# as3320-Vowel-1.net
KiCad netlist of a schematic drawn in EAGLE
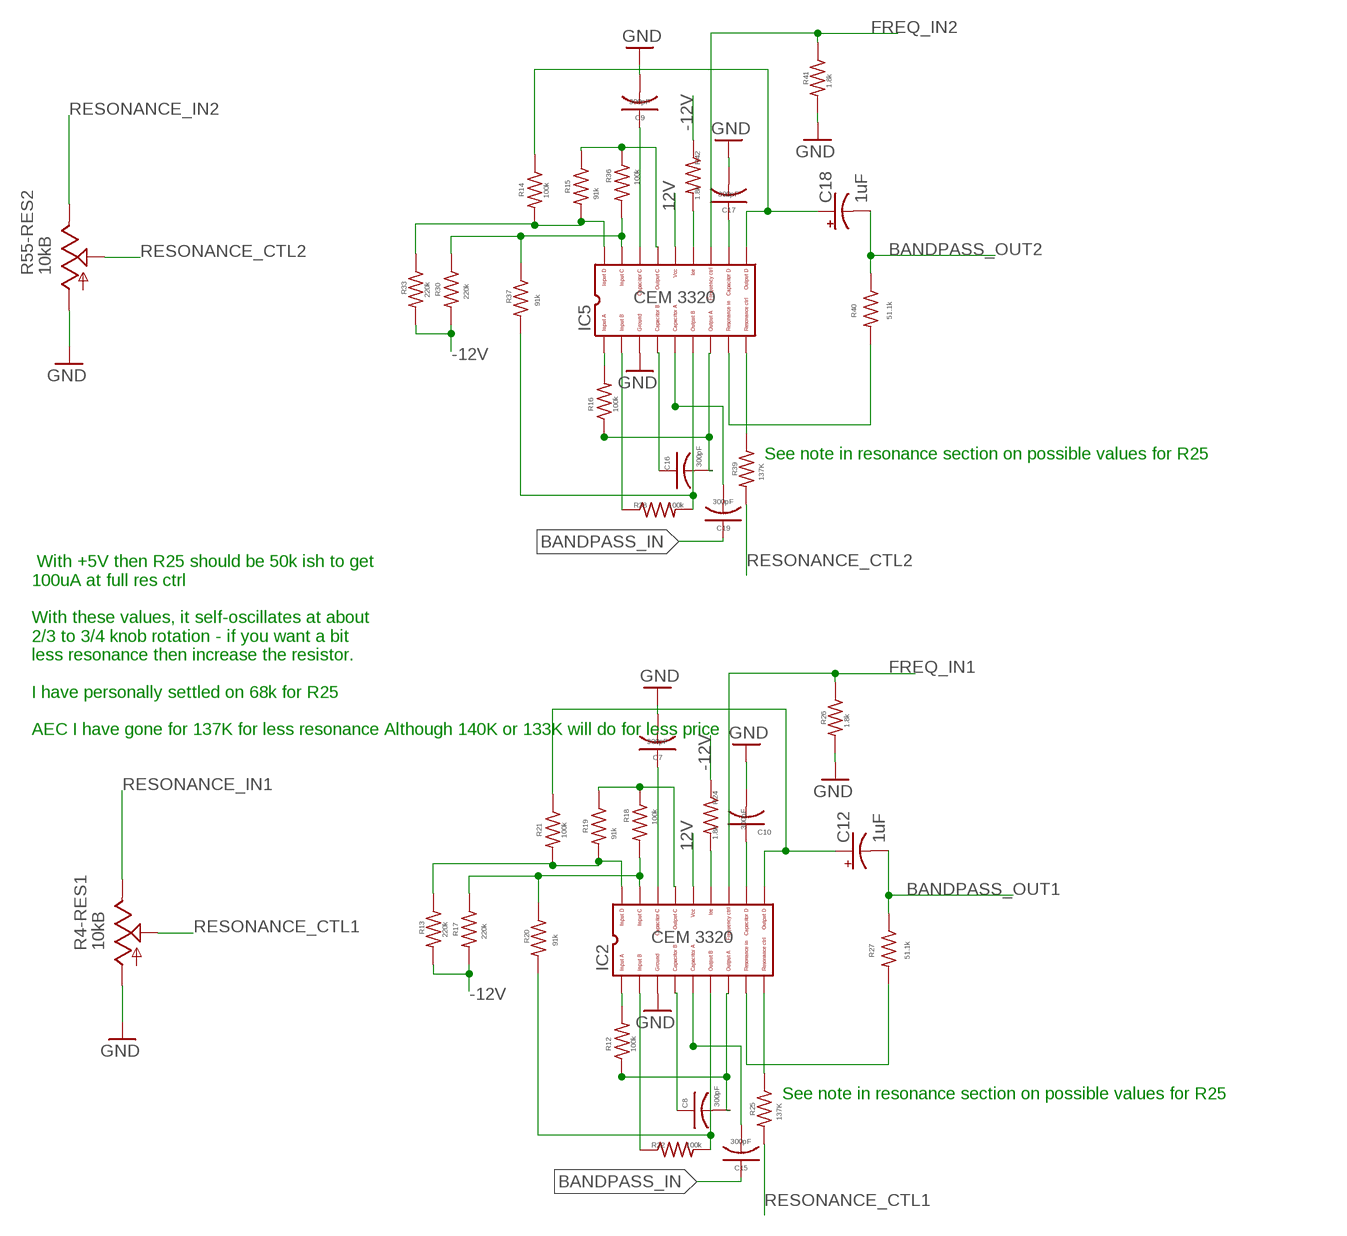
[diagram p0: schematic, sheet 1, part 1 of 2]
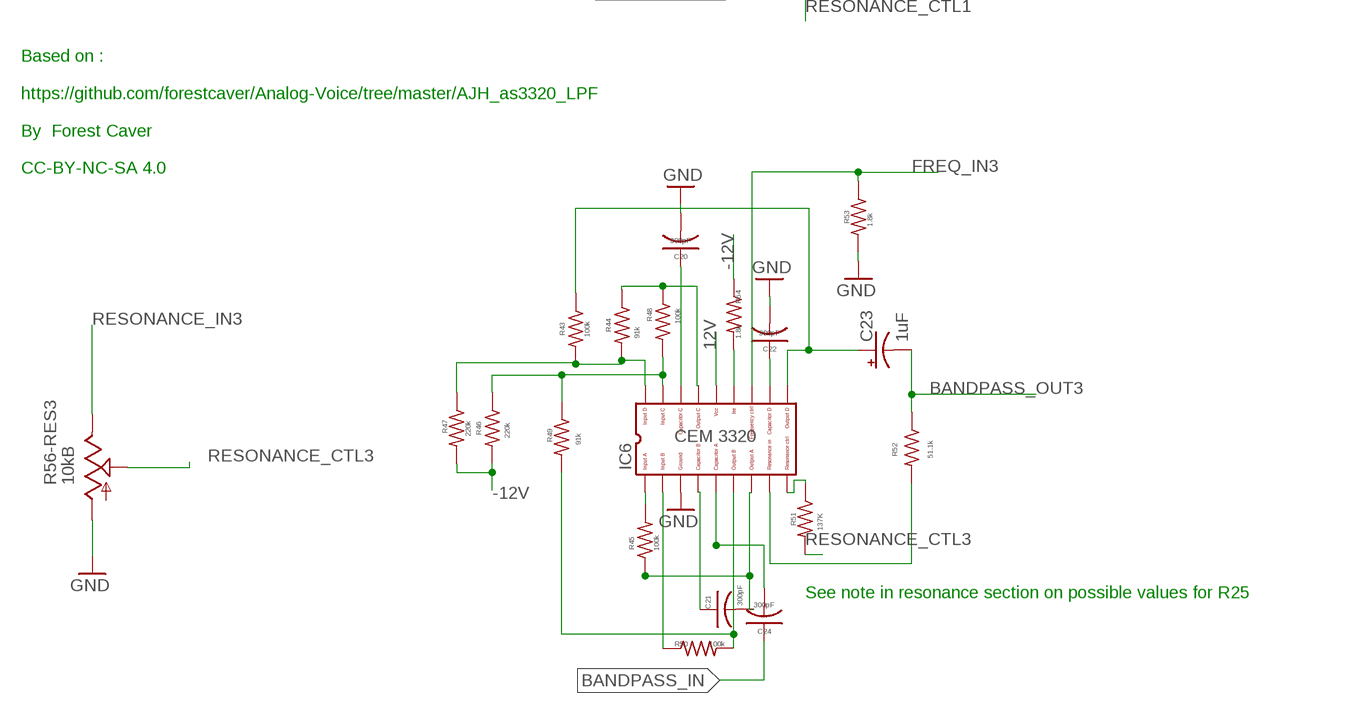
[diagram p1: schematic, sheet 1, part 2 of 2]
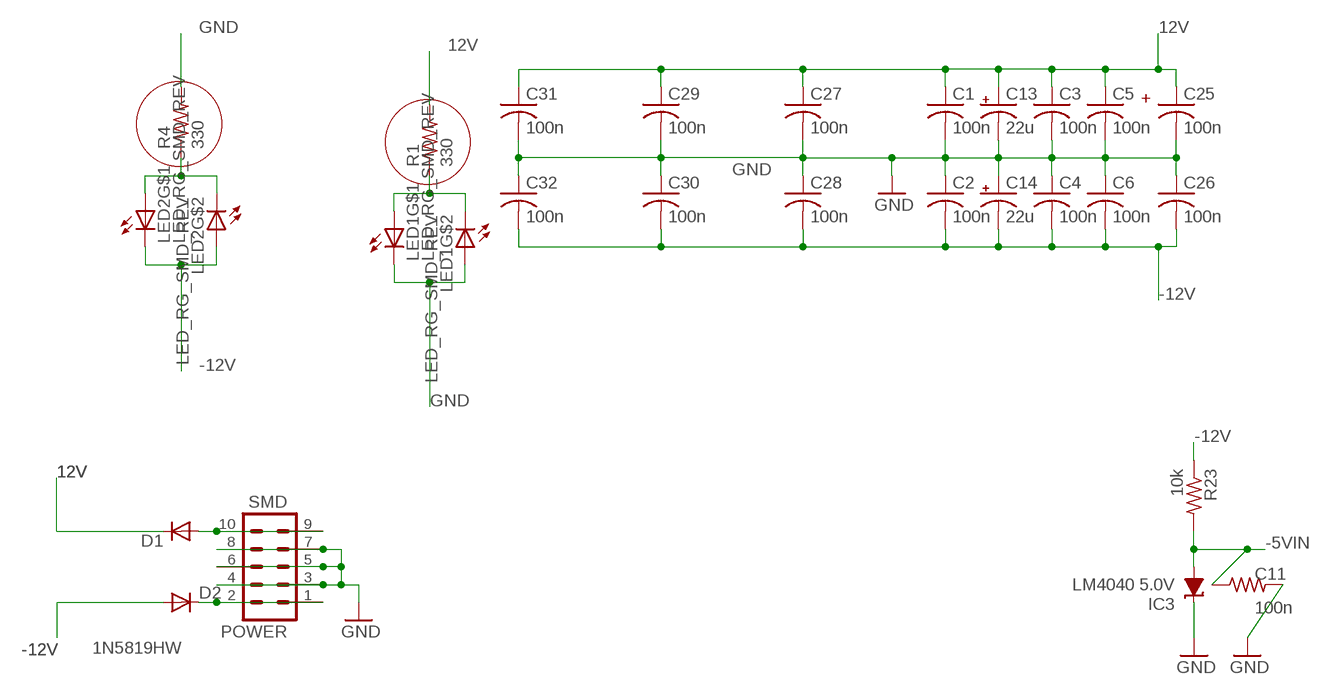
[diagram p2: schematic, sheet 2]
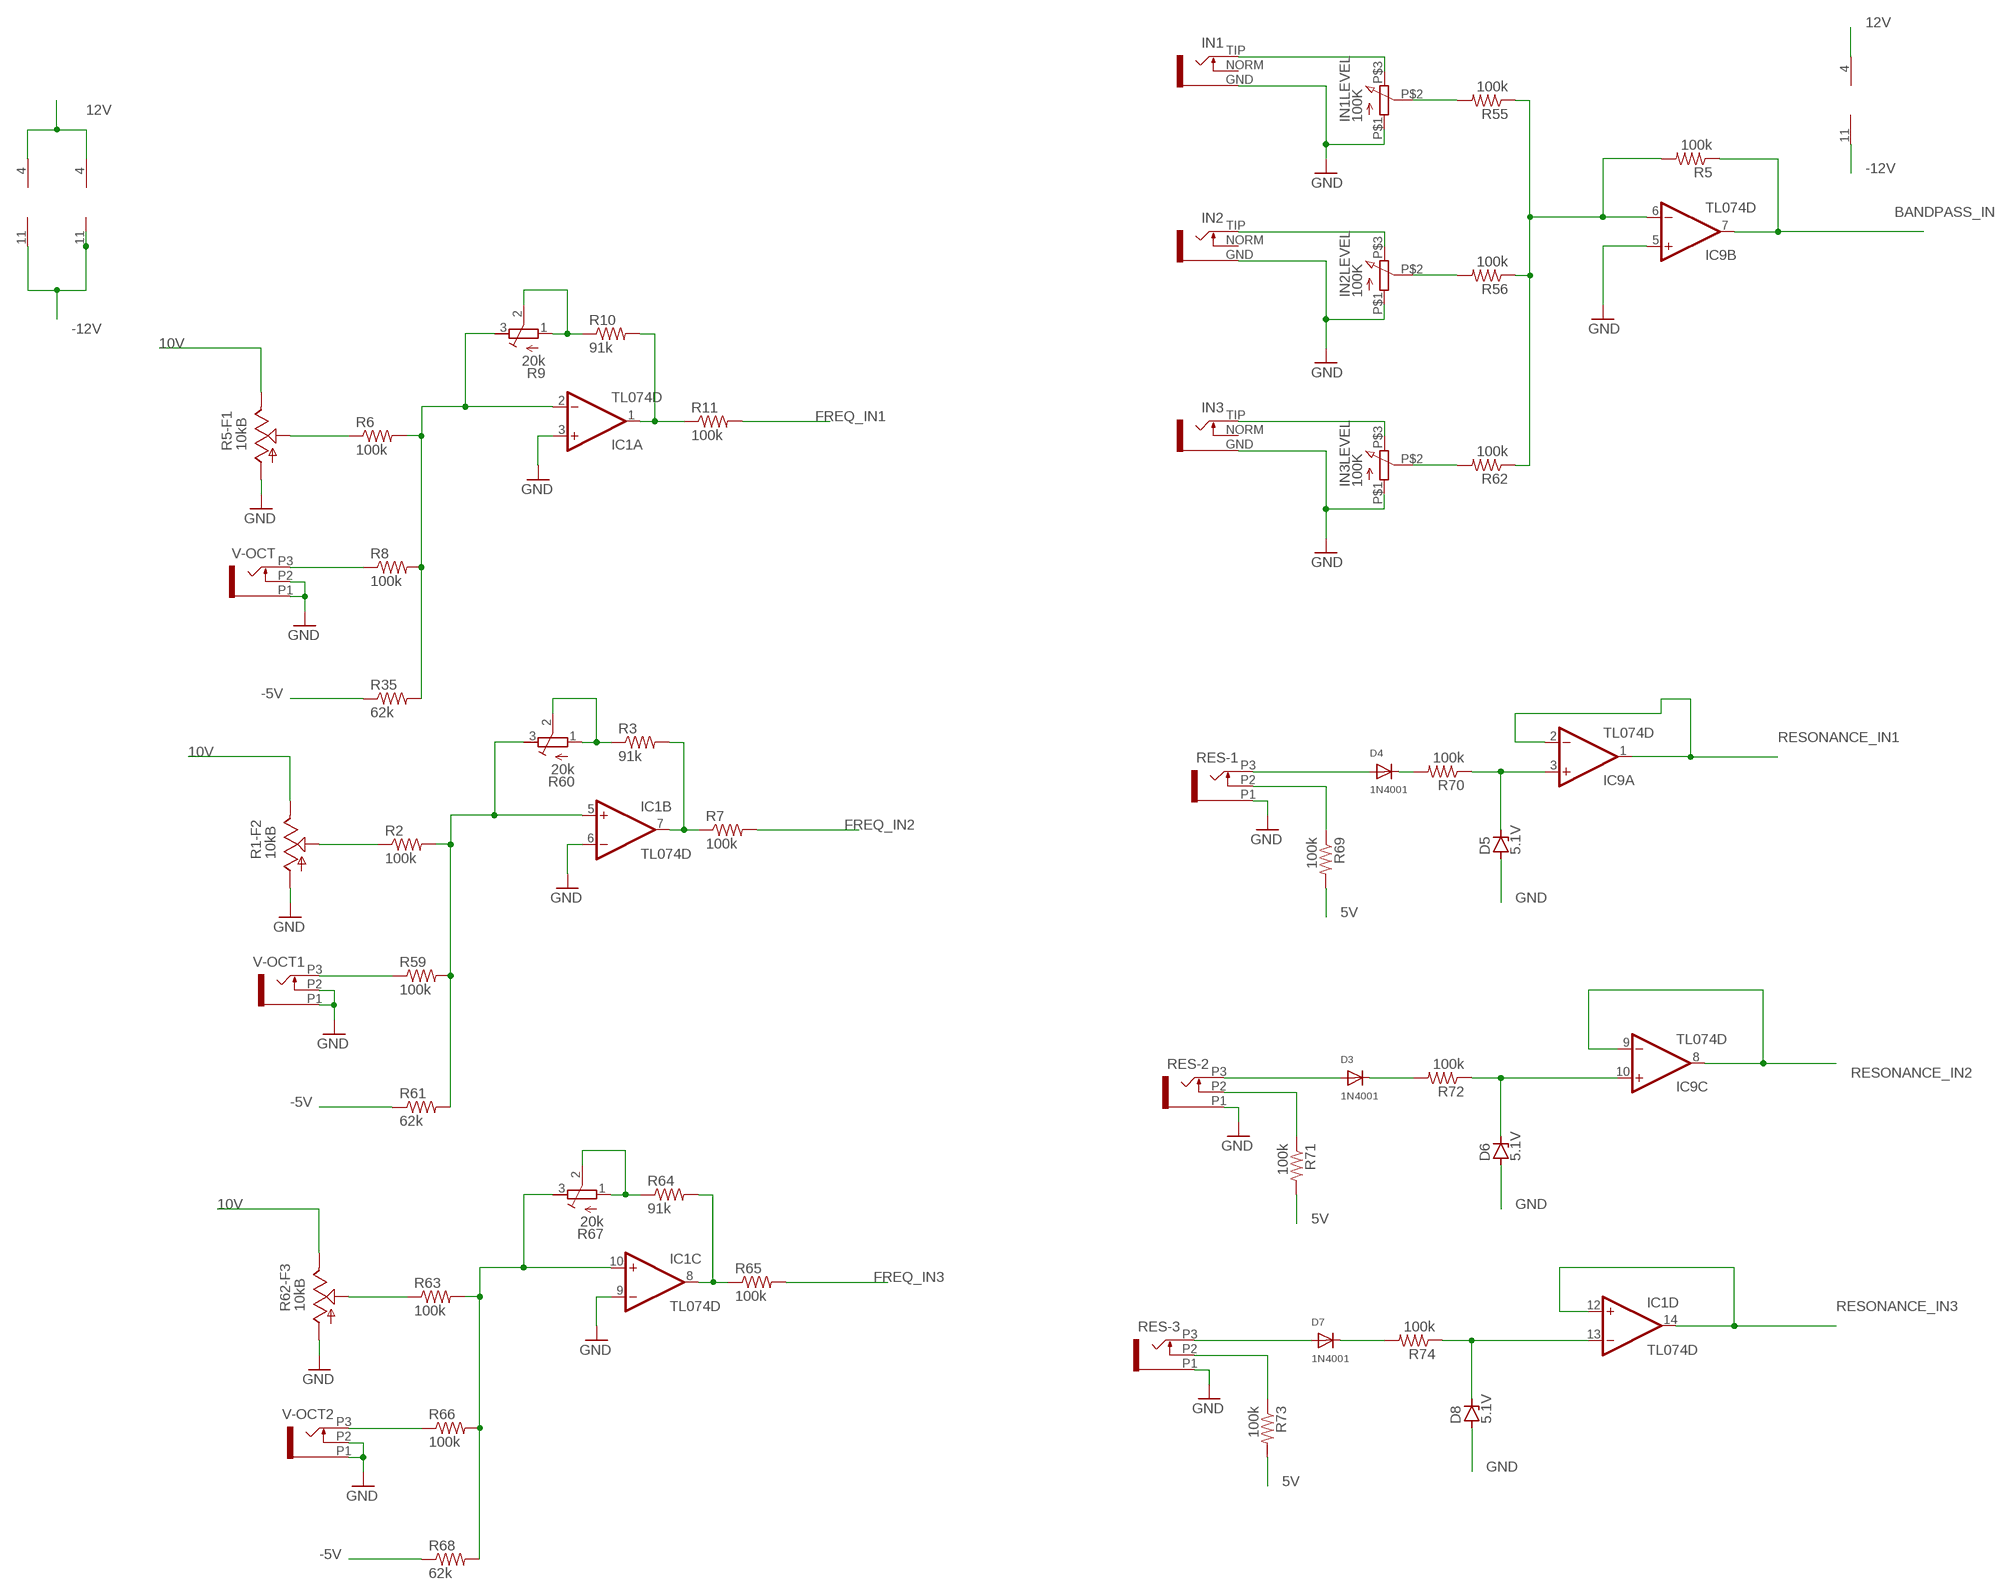
[diagram p3: schematic, sheet 3]
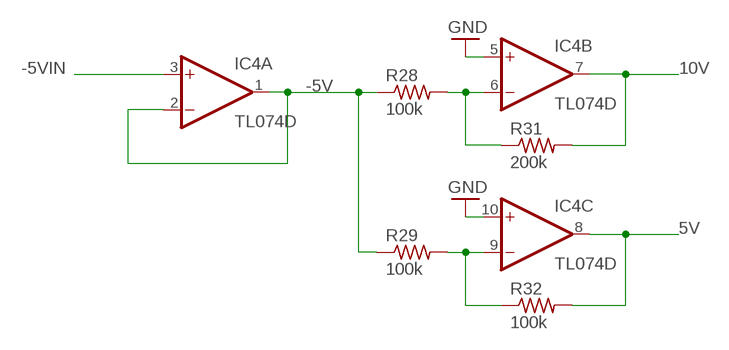
[diagram p4: schematic, sheet 4]
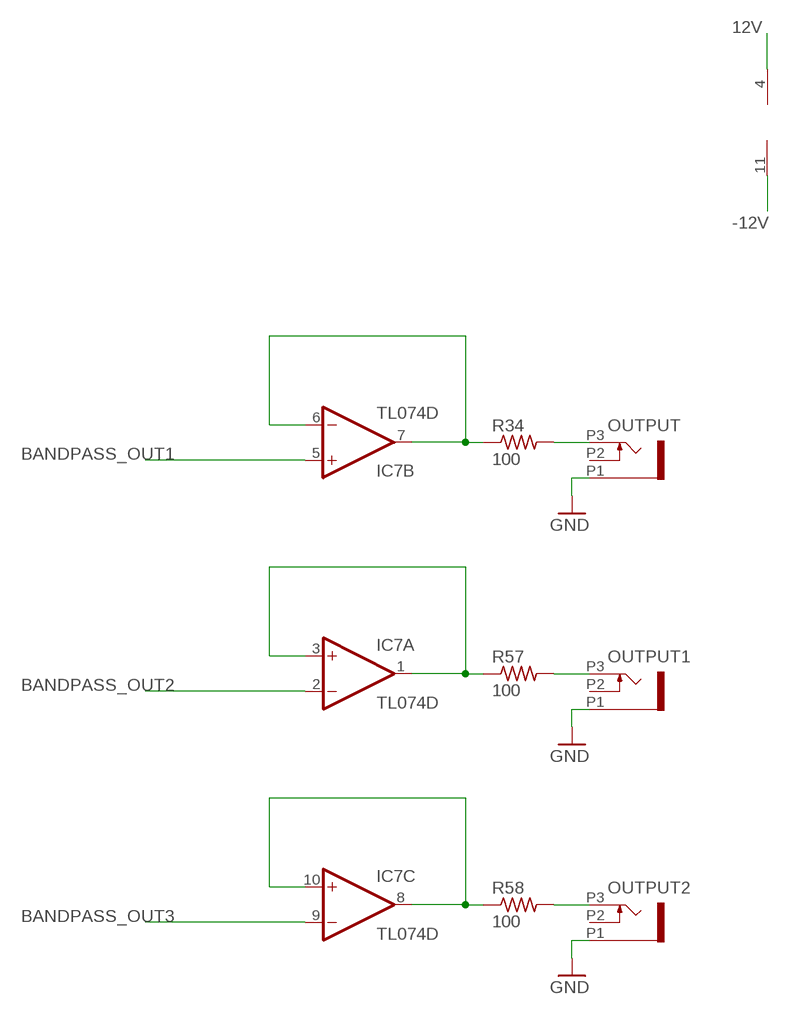
[diagram p5: schematic, sheet 5]

(export (version "E")
  (design (tool "Eeschema 10.0.6"))
  (components
    (comp (ref "IC4")
      (value "TL074D")
      (footprint "eagle-import:SO14")
      (libsource (lib "eagle-import") (part "linear_262_TL074D"))
    )
    (comp (ref "R28")
      (value "100k")
      (footprint "eagle-import:GMSN_M0805")
      (libsource (lib "eagle-import") (part "GMSN_R-US_M0805"))
    )
    (comp (ref "R29")
      (value "100k")
      (footprint "eagle-import:GMSN_M0805")
      (libsource (lib "eagle-import") (part "GMSN_R-US_M0805"))
    )
    (comp (ref "R31")
      (value "200k")
      (footprint "eagle-import:GMSN_M0805")
      (libsource (lib "eagle-import") (part "GMSN_R-US_M0805"))
    )
    (comp (ref "R32")
      (value "100k")
      (footprint "eagle-import:GMSN_M0805")
      (libsource (lib "eagle-import") (part "GMSN_R-US_M0805"))
    )
    (comp (ref "C1")
      (value "100n")
      (footprint "eagle-import:C0805K")
      (libsource (lib "eagle-import") (part "C-USC0805K"))
    )
    (comp (ref "C2")
      (value "100n")
      (footprint "eagle-import:C0805K")
      (libsource (lib "eagle-import") (part "C-USC0805K"))
    )
    (comp (ref "C3")
      (value "100n")
      (footprint "eagle-import:C0805K")
      (libsource (lib "eagle-import") (part "C-USC0805K"))
    )
    (comp (ref "C4")
      (value "100n")
      (footprint "eagle-import:C0805K")
      (libsource (lib "eagle-import") (part "C-USC0805K"))
    )
    (comp (ref "C5")
      (value "100n")
      (footprint "eagle-import:C0805K")
      (libsource (lib "eagle-import") (part "C-USC0805K"))
    )
    (comp (ref "C6")
      (value "100n")
      (footprint "eagle-import:C0805K")
      (libsource (lib "eagle-import") (part "C-USC0805K"))
    )
    (comp (ref "C11")
      (value "100n")
      (footprint "eagle-import:GMSN_M0805")
      (libsource (lib "eagle-import") (part "GMSN_R-US_M0805"))
    )
    (comp (ref "C13")
      (value "22u")
      (footprint "eagle-import:PANASONIC_B")
      (libsource (lib "eagle-import") (part "CPOL-USB"))
    )
    (comp (ref "C14")
      (value "22u")
      (footprint "eagle-import:PANASONIC_B")
      (libsource (lib "eagle-import") (part "CPOL-USB"))
    )
    (comp (ref "C25")
      (value "100n")
      (footprint "eagle-import:C0805K")
      (libsource (lib "eagle-import") (part "C-USC0805K"))
    )
    (comp (ref "C26")
      (value "100n")
      (footprint "eagle-import:C0805K")
      (libsource (lib "eagle-import") (part "C-USC0805K"))
    )
    (comp (ref "C27")
      (value "100n")
      (footprint "eagle-import:C0805K")
      (libsource (lib "eagle-import") (part "C-USC0805K"))
    )
    (comp (ref "C28")
      (value "100n")
      (footprint "eagle-import:C0805K")
      (libsource (lib "eagle-import") (part "C-USC0805K"))
    )
    (comp (ref "C29")
      (value "100n")
      (footprint "eagle-import:C0805K")
      (libsource (lib "eagle-import") (part "C-USC0805K"))
    )
    (comp (ref "C30")
      (value "100n")
      (footprint "eagle-import:C0805K")
      (libsource (lib "eagle-import") (part "C-USC0805K"))
    )
    (comp (ref "C31")
      (value "100n")
      (footprint "eagle-import:C0805K")
      (libsource (lib "eagle-import") (part "C-USC0805K"))
    )
    (comp (ref "C32")
      (value "100n")
      (footprint "eagle-import:C0805K")
      (libsource (lib "eagle-import") (part "C-USC0805K"))
    )
    (comp (ref "D1")
      (value "1N5819HW")
      (footprint "eagle-import:SOD123")
      (libsource (lib "eagle-import") (part "DIODE-SOD123"))
    )
    (comp (ref "D2")
      (value "1N5819HW")
      (footprint "eagle-import:SOD123")
      (libsource (lib "eagle-import") (part "DIODE-SOD123"))
    )
    (comp (ref "IC3")
      (value "LM4040 5.0V")
      (footprint "eagle-import:DBZ_R-PDSO-G3")
      (libsource (lib "eagle-import") (part "LM4041DBZC12"))
    )
    (comp (ref "LED1")
      (value "LED_RG_SMD_REV")
      (footprint "eagle-import:LSG_T77K")
      (fields (field (name "RS-PART") "915-4828"))
      (libsource (lib "eagle-import") (part "LED_RG_SMD_REV"))
    )
    (comp (ref "LED2")
      (value "LED_RG_SMD_REV")
      (footprint "eagle-import:LSG_T77K")
      (libsource (lib "eagle-import") (part "LED_RG_SMD_REV"))
    )
    (comp (ref "POWER")
      (value "SMD")
      (footprint "eagle-import:2X5-SHROUDED_SMD")
      (fields (field (name "RS-PART") "828-1783"))
      (libsource (lib "eagle-import") (part "CONN_05X2SHD_SMD"))
    )
    (comp (ref "R1")
      (value "330")
      (footprint "eagle-import:GMSN_M0805")
      (libsource (lib "eagle-import") (part "GMSN_R-US_M0805"))
    )
    (comp (ref "R4")
      (value "330")
      (footprint "eagle-import:GMSN_M0805")
      (fields (field (name "RS-PART") "915-4828"))
      (libsource (lib "eagle-import") (part "GMSN_R-US_M0805"))
    )
    (comp (ref "R23")
      (value "10k")
      (footprint "eagle-import:GMSN_M0805")
      (libsource (lib "eagle-import") (part "GMSN_R-US_M0805"))
    )
    (comp (ref "C7")
      (value "300pF")
      (footprint "eagle-import:C0805K")
      (libsource (lib "eagle-import") (part "C-USC0805K"))
    )
    (comp (ref "C8")
      (value "300pF")
      (footprint "eagle-import:C0805K")
      (libsource (lib "eagle-import") (part "C-USC0805K"))
    )
    (comp (ref "C9")
      (value "300pF")
      (footprint "eagle-import:C0805K")
      (libsource (lib "eagle-import") (part "C-USC0805K"))
    )
    (comp (ref "C10")
      (value "300pF")
      (footprint "eagle-import:GMSN_C0805K")
      (libsource (lib "eagle-import") (part "GMSN_C-USC0805K"))
    )
    (comp (ref "C12")
      (value "1uF")
      (footprint "eagle-import:PANASONIC_B")
      (libsource (lib "eagle-import") (part "rcl_334_CPOL-USB"))
    )
    (comp (ref "C15")
      (value "300pF")
      (footprint "eagle-import:C0805K")
      (libsource (lib "eagle-import") (part "C-USC0805K"))
    )
    (comp (ref "C16")
      (value "300pF")
      (footprint "eagle-import:C0805K")
      (libsource (lib "eagle-import") (part "C-USC0805K"))
    )
    (comp (ref "C17")
      (value "300pF")
      (footprint "eagle-import:C0805K")
      (libsource (lib "eagle-import") (part "C-USC0805K"))
    )
    (comp (ref "C18")
      (value "1uF")
      (footprint "eagle-import:PANASONIC_B")
      (libsource (lib "eagle-import") (part "rcl_334_CPOL-USB"))
    )
    (comp (ref "C19")
      (value "300pF")
      (footprint "eagle-import:C0805K")
      (libsource (lib "eagle-import") (part "C-USC0805K"))
    )
    (comp (ref "C20")
      (value "300pF")
      (footprint "eagle-import:C0805K")
      (libsource (lib "eagle-import") (part "C-USC0805K"))
    )
    (comp (ref "C21")
      (value "300pF")
      (footprint "eagle-import:C0805K")
      (libsource (lib "eagle-import") (part "C-USC0805K"))
    )
    (comp (ref "C22")
      (value "300pF")
      (footprint "eagle-import:C0805K")
      (libsource (lib "eagle-import") (part "C-USC0805K"))
    )
    (comp (ref "C23")
      (value "1uF")
      (footprint "eagle-import:PANASONIC_B")
      (libsource (lib "eagle-import") (part "rcl_334_CPOL-USB"))
    )
    (comp (ref "C24")
      (value "300pF")
      (footprint "eagle-import:GMSN_C0805K")
      (libsource (lib "eagle-import") (part "GMSN_C-USC0805K"))
    )
    (comp (ref "IC2")
      (value "CEM3320")
      (footprint "eagle-import:DIL18")
      (libsource (lib "eagle-import") (part "CEM3320"))
    )
    (comp (ref "IC5")
      (value "CEM3320")
      (footprint "eagle-import:DIL18")
      (libsource (lib "eagle-import") (part "CEM3320"))
    )
    (comp (ref "IC6")
      (value "CEM3320")
      (footprint "eagle-import:DIL18")
      (libsource (lib "eagle-import") (part "CEM3320"))
    )
    (comp (ref "R4-RES1")
      (value "10kB")
      (footprint "eagle-import:ALPS_POT_VERTICAL")
      (libsource (lib "eagle-import") (part "POT_USVERTICAL"))
    )
    (comp (ref "R12")
      (value "100k")
      (footprint "eagle-import:GMSN_M0805")
      (libsource (lib "eagle-import") (part "GMSN_R-US_M0805"))
    )
    (comp (ref "R13")
      (value "220k")
      (footprint "eagle-import:GMSN_M0805")
      (libsource (lib "eagle-import") (part "GMSN_R-US_M0805"))
    )
    (comp (ref "R14")
      (value "100k")
      (footprint "eagle-import:GMSN_M0805")
      (libsource (lib "eagle-import") (part "GMSN_R-US_M0805"))
    )
    (comp (ref "R15")
      (value "91k")
      (footprint "eagle-import:GMSN_M0805")
      (libsource (lib "eagle-import") (part "GMSN_R-US_M0805"))
    )
    (comp (ref "R16")
      (value "100k")
      (footprint "eagle-import:GMSN_M0805")
      (libsource (lib "eagle-import") (part "GMSN_R-US_M0805"))
    )
    (comp (ref "R17")
      (value "220k")
      (footprint "eagle-import:GMSN_M0805")
      (libsource (lib "eagle-import") (part "GMSN_R-US_M0805"))
    )
    (comp (ref "R18")
      (value "100k")
      (footprint "eagle-import:GMSN_M0805")
      (libsource (lib "eagle-import") (part "GMSN_R-US_M0805"))
    )
    (comp (ref "R19")
      (value "91k")
      (footprint "eagle-import:GMSN_M0805")
      (libsource (lib "eagle-import") (part "GMSN_R-US_M0805"))
    )
    (comp (ref "R20")
      (value "91k")
      (footprint "eagle-import:GMSN_M0805")
      (libsource (lib "eagle-import") (part "GMSN_R-US_M0805"))
    )
    (comp (ref "R21")
      (value "100k")
      (footprint "eagle-import:GMSN_M0805")
      (libsource (lib "eagle-import") (part "GMSN_R-US_M0805"))
    )
    (comp (ref "R22")
      (value "100k")
      (footprint "eagle-import:GMSN_M0805")
      (libsource (lib "eagle-import") (part "GMSN_R-US_M0805"))
    )
    (comp (ref "R24")
      (value "1.8k")
      (footprint "eagle-import:GMSN_M0805")
      (libsource (lib "eagle-import") (part "GMSN_R-US_M0805"))
    )
    (comp (ref "R25")
      (value "137K")
      (footprint "eagle-import:GMSN_M0805")
      (libsource (lib "eagle-import") (part "GMSN_R-US_M0805"))
    )
    (comp (ref "R26")
      (value "1.8k")
      (footprint "eagle-import:GMSN_M0805")
      (libsource (lib "eagle-import") (part "GMSN_R-US_M0805"))
    )
    (comp (ref "R27")
      (value "51.1k")
      (footprint "eagle-import:GMSN_M0805")
      (libsource (lib "eagle-import") (part "GMSN_R-US_M0805"))
    )
    (comp (ref "R30")
      (value "220k")
      (footprint "eagle-import:GMSN_M0805")
      (libsource (lib "eagle-import") (part "GMSN_R-US_M0805"))
    )
    (comp (ref "R33")
      (value "220k")
      (footprint "eagle-import:GMSN_M0805")
      (libsource (lib "eagle-import") (part "GMSN_R-US_M0805"))
    )
    (comp (ref "R36")
      (value "100k")
      (footprint "eagle-import:GMSN_M0805")
      (libsource (lib "eagle-import") (part "GMSN_R-US_M0805"))
    )
    (comp (ref "R37")
      (value "91k")
      (footprint "eagle-import:GMSN_M0805")
      (libsource (lib "eagle-import") (part "GMSN_R-US_M0805"))
    )
    (comp (ref "R38")
      (value "100k")
      (footprint "eagle-import:GMSN_M0805")
      (libsource (lib "eagle-import") (part "GMSN_R-US_M0805"))
    )
    (comp (ref "R39")
      (value "137K")
      (footprint "eagle-import:GMSN_M0805")
      (libsource (lib "eagle-import") (part "GMSN_R-US_M0805"))
    )
    (comp (ref "R40")
      (value "51.1k")
      (footprint "eagle-import:GMSN_M0805")
      (libsource (lib "eagle-import") (part "GMSN_R-US_M0805"))
    )
    (comp (ref "R41")
      (value "1.8k")
      (footprint "eagle-import:GMSN_M0805")
      (libsource (lib "eagle-import") (part "GMSN_R-US_M0805"))
    )
    (comp (ref "R42")
      (value "1.8k")
      (footprint "eagle-import:GMSN_M0805")
      (libsource (lib "eagle-import") (part "GMSN_R-US_M0805"))
    )
    (comp (ref "R43")
      (value "100k")
      (footprint "eagle-import:GMSN_M0805")
      (libsource (lib "eagle-import") (part "GMSN_R-US_M0805"))
    )
    (comp (ref "R44")
      (value "91k")
      (footprint "eagle-import:GMSN_M0805")
      (libsource (lib "eagle-import") (part "GMSN_R-US_M0805"))
    )
    (comp (ref "R45")
      (value "100k")
      (footprint "eagle-import:GMSN_M0805")
      (libsource (lib "eagle-import") (part "GMSN_R-US_M0805"))
    )
    (comp (ref "R46")
      (value "220k")
      (footprint "eagle-import:GMSN_M0805")
      (libsource (lib "eagle-import") (part "GMSN_R-US_M0805"))
    )
    (comp (ref "R47")
      (value "220k")
      (footprint "eagle-import:GMSN_M0805")
      (libsource (lib "eagle-import") (part "GMSN_R-US_M0805"))
    )
    (comp (ref "R48")
      (value "100k")
      (footprint "eagle-import:GMSN_M0805")
      (libsource (lib "eagle-import") (part "GMSN_R-US_M0805"))
    )
    (comp (ref "R49")
      (value "91k")
      (footprint "eagle-import:GMSN_M0805")
      (libsource (lib "eagle-import") (part "GMSN_R-US_M0805"))
    )
    (comp (ref "R50")
      (value "100k")
      (footprint "eagle-import:GMSN_M0805")
      (libsource (lib "eagle-import") (part "GMSN_R-US_M0805"))
    )
    (comp (ref "R51")
      (value "137K")
      (footprint "eagle-import:GMSN_M0805")
      (libsource (lib "eagle-import") (part "GMSN_R-US_M0805"))
    )
    (comp (ref "R52")
      (value "51.1k")
      (footprint "eagle-import:GMSN_M0805")
      (libsource (lib "eagle-import") (part "GMSN_R-US_M0805"))
    )
    (comp (ref "R53")
      (value "1.8k")
      (footprint "eagle-import:GMSN_M0805")
      (libsource (lib "eagle-import") (part "GMSN_R-US_M0805"))
    )
    (comp (ref "R54")
      (value "1.8k")
      (footprint "eagle-import:GMSN_M0805")
      (libsource (lib "eagle-import") (part "GMSN_R-US_M0805"))
    )
    (comp (ref "R55-RES2")
      (value "10kB")
      (footprint "eagle-import:ALPS_POT_VERTICAL")
      (libsource (lib "eagle-import") (part "POT_USVERTICAL"))
    )
    (comp (ref "R56-RES3")
      (value "10kB")
      (footprint "eagle-import:ALPS_POT_VERTICAL")
      (libsource (lib "eagle-import") (part "POT_USVERTICAL"))
    )
    (comp (ref "D3")
      (value "1N4001")
      (footprint "eagle-import:SMADIODE")
      (libsource (lib "eagle-import") (part "DIODESMA"))
    )
    (comp (ref "D4")
      (value "1N4001")
      (footprint "eagle-import:SMADIODE")
      (libsource (lib "eagle-import") (part "DIODESMA"))
    )
    (comp (ref "D5")
      (value "5.1V")
      (footprint "eagle-import:SOT23")
      (fields (field (name "RS-PART") "816-7962"))
      (libsource (lib "eagle-import") (part "ZENER-DIODESOT23"))
    )
    (comp (ref "D6")
      (value "5.1V")
      (footprint "eagle-import:SOT23")
      (fields (field (name "RS-PART") "816-7962"))
      (libsource (lib "eagle-import") (part "ZENER-DIODESOT23"))
    )
    (comp (ref "D7")
      (value "1N4001")
      (footprint "eagle-import:SMADIODE")
      (libsource (lib "eagle-import") (part "DIODESMA"))
    )
    (comp (ref "D8")
      (value "5.1V")
      (footprint "eagle-import:SOT23")
      (fields (field (name "RS-PART") "816-7962"))
      (libsource (lib "eagle-import") (part "ZENER-DIODESOT23"))
    )
    (comp (ref "IC1")
      (value "TL074D")
      (footprint "eagle-import:SO14")
      (libsource (lib "eagle-import") (part "linear_262_TL074D"))
    )
    (comp (ref "IC9")
      (value "TL074D")
      (footprint "eagle-import:SO14")
      (libsource (lib "eagle-import") (part "TL074D"))
    )
    (comp (ref "IN1")
      (value "S_JACK")
      (footprint "eagle-import:S_JACK")
      (libsource (lib "eagle-import") (part "S_JACK"))
    )
    (comp (ref "IN1LEVEL")
      (value "100K")
      (footprint "eagle-import:POT")
      (libsource (lib "eagle-import") (part "9MMPOT"))
    )
    (comp (ref "IN2")
      (value "S_JACK")
      (footprint "eagle-import:S_JACK")
      (libsource (lib "eagle-import") (part "S_JACK"))
    )
    (comp (ref "IN2LEVEL")
      (value "100K")
      (footprint "eagle-import:POT")
      (libsource (lib "eagle-import") (part "9MMPOT"))
    )
    (comp (ref "IN3")
      (value "S_JACK")
      (footprint "eagle-import:S_JACK")
      (libsource (lib "eagle-import") (part "S_JACK"))
    )
    (comp (ref "IN3LEVEL")
      (value "100K")
      (footprint "eagle-import:POT")
      (libsource (lib "eagle-import") (part "9MMPOT"))
    )
    (comp (ref "R1-F2")
      (value "10kB")
      (footprint "eagle-import:ALPS_POT_VERTICAL")
      (libsource (lib "eagle-import") (part "POT_USVERTICAL"))
    )
    (comp (ref "R2")
      (value "100k")
      (footprint "eagle-import:GMSN_M0805")
      (libsource (lib "eagle-import") (part "GMSN_R-US_M0805"))
    )
    (comp (ref "R3")
      (value "91k")
      (footprint "eagle-import:GMSN_M0805")
      (libsource (lib "eagle-import") (part "GMSN_R-US_M0805"))
    )
    (comp (ref "R5")
      (value "100k")
      (footprint "eagle-import:GMSN_M0805")
      (libsource (lib "eagle-import") (part "GMSN_R-US_M0805"))
    )
    (comp (ref "R5-F1")
      (value "10kB")
      (footprint "eagle-import:ALPS_POT_VERTICAL")
      (libsource (lib "eagle-import") (part "POT_USVERTICAL"))
    )
    (comp (ref "R6")
      (value "100k")
      (footprint "eagle-import:GMSN_M0805")
      (libsource (lib "eagle-import") (part "GMSN_R-US_M0805"))
    )
    (comp (ref "R7")
      (value "100k")
      (footprint "eagle-import:GMSN_M0805")
      (libsource (lib "eagle-import") (part "GMSN_R-US_M0805"))
    )
    (comp (ref "R8")
      (value "100k")
      (footprint "eagle-import:GMSN_M0805")
      (libsource (lib "eagle-import") (part "GMSN_R-US_M0805"))
    )
    (comp (ref "R9")
      (value "20k")
      (footprint "eagle-import:RTRIM3296X")
      (libsource (lib "eagle-import") (part "R-TRIMM3296X"))
    )
    (comp (ref "R10")
      (value "91k")
      (footprint "eagle-import:GMSN_M0805")
      (libsource (lib "eagle-import") (part "GMSN_R-US_M0805"))
    )
    (comp (ref "R11")
      (value "100k")
      (footprint "eagle-import:GMSN_M0805")
      (libsource (lib "eagle-import") (part "GMSN_R-US_M0805"))
    )
    (comp (ref "R35")
      (value "62k")
      (footprint "eagle-import:GMSN_M0805")
      (libsource (lib "eagle-import") (part "GMSN_R-US_M0805"))
    )
    (comp (ref "R55")
      (value "100k")
      (footprint "eagle-import:R0805")
      (libsource (lib "eagle-import") (part "GMSN_R-US_R0805"))
    )
    (comp (ref "R56")
      (value "100k")
      (footprint "eagle-import:R0805")
      (libsource (lib "eagle-import") (part "GMSN_R-US_R0805"))
    )
    (comp (ref "R59")
      (value "100k")
      (footprint "eagle-import:GMSN_M0805")
      (libsource (lib "eagle-import") (part "GMSN_R-US_M0805"))
    )
    (comp (ref "R60")
      (value "20k")
      (footprint "eagle-import:RTRIM3296X")
      (libsource (lib "eagle-import") (part "R-TRIMM3296X"))
    )
    (comp (ref "R61")
      (value "62k")
      (footprint "eagle-import:GMSN_M0805")
      (libsource (lib "eagle-import") (part "GMSN_R-US_M0805"))
    )
    (comp (ref "R62")
      (value "100k")
      (footprint "eagle-import:R0805")
      (libsource (lib "eagle-import") (part "GMSN_R-US_R0805"))
    )
    (comp (ref "R62-F3")
      (value "10kB")
      (footprint "eagle-import:ALPS_POT_VERTICAL")
      (libsource (lib "eagle-import") (part "POT_USVERTICAL"))
    )
    (comp (ref "R63")
      (value "100k")
      (footprint "eagle-import:GMSN_M0805")
      (libsource (lib "eagle-import") (part "GMSN_R-US_M0805"))
    )
    (comp (ref "R64")
      (value "91k")
      (footprint "eagle-import:GMSN_M0805")
      (libsource (lib "eagle-import") (part "GMSN_R-US_M0805"))
    )
    (comp (ref "R65")
      (value "100k")
      (footprint "eagle-import:GMSN_M0805")
      (libsource (lib "eagle-import") (part "GMSN_R-US_M0805"))
    )
    (comp (ref "R66")
      (value "100k")
      (footprint "eagle-import:GMSN_M0805")
      (libsource (lib "eagle-import") (part "GMSN_R-US_M0805"))
    )
    (comp (ref "R67")
      (value "20k")
      (footprint "eagle-import:RTRIM3296X")
      (libsource (lib "eagle-import") (part "R-TRIMM3296X"))
    )
    (comp (ref "R68")
      (value "62k")
      (footprint "eagle-import:GMSN_M0805")
      (libsource (lib "eagle-import") (part "GMSN_R-US_M0805"))
    )
    (comp (ref "R69")
      (value "100k")
      (footprint "eagle-import:R0805")
      (libsource (lib "eagle-import") (part "GMSN_R-US_R0805"))
    )
    (comp (ref "R70")
      (value "100k")
      (footprint "eagle-import:GMSN_M0805")
      (libsource (lib "eagle-import") (part "GMSN_R-US_M0805"))
    )
    (comp (ref "R71")
      (value "100k")
      (footprint "eagle-import:R0805")
      (libsource (lib "eagle-import") (part "GMSN_R-US_R0805"))
    )
    (comp (ref "R72")
      (value "100k")
      (footprint "eagle-import:GMSN_M0805")
      (libsource (lib "eagle-import") (part "GMSN_R-US_M0805"))
    )
    (comp (ref "R73")
      (value "100k")
      (footprint "eagle-import:R0805")
      (libsource (lib "eagle-import") (part "GMSN_R-US_R0805"))
    )
    (comp (ref "R74")
      (value "100k")
      (footprint "eagle-import:R0805")
      (libsource (lib "eagle-import") (part "GMSN_R-US_R0805"))
    )
    (comp (ref "RES-1")
      (value "PJ301_THONKICONN6")
      (footprint "eagle-import:WQP_PJ_301M6")
      (libsource (lib "eagle-import") (part "PJ301_THONKICONN6"))
    )
    (comp (ref "RES-2")
      (value "PJ301_THONKICONN6")
      (footprint "eagle-import:WQP_PJ_301M6")
      (libsource (lib "eagle-import") (part "PJ301_THONKICONN6"))
    )
    (comp (ref "RES-3")
      (value "PJ301_THONKICONN6")
      (footprint "eagle-import:WQP_PJ_301M6")
      (libsource (lib "eagle-import") (part "PJ301_THONKICONN6"))
    )
    (comp (ref "V-OCT")
      (value "PJ301_THONKICONN6")
      (footprint "eagle-import:WQP_PJ_301M6")
      (libsource (lib "eagle-import") (part "PJ301_THONKICONN6"))
    )
    (comp (ref "V-OCT1")
      (value "PJ301_THONKICONN6")
      (footprint "eagle-import:WQP_PJ_301M6")
      (libsource (lib "eagle-import") (part "PJ301_THONKICONN6"))
    )
    (comp (ref "V-OCT2")
      (value "PJ301_THONKICONN6")
      (footprint "eagle-import:WQP_PJ_301M6")
      (libsource (lib "eagle-import") (part "PJ301_THONKICONN6"))
    )
    (comp (ref "IC7")
      (value "TL074D")
      (footprint "eagle-import:SO14")
      (libsource (lib "eagle-import") (part "linear_262_TL074D"))
    )
    (comp (ref "OUTPUT")
      (value "PJ301_THONKICONN6")
      (footprint "eagle-import:WQP_PJ_301M6")
      (libsource (lib "eagle-import") (part "PJ301_THONKICONN6"))
    )
    (comp (ref "OUTPUT1")
      (value "PJ301_THONKICONN6")
      (footprint "eagle-import:WQP_PJ_301M6")
      (libsource (lib "eagle-import") (part "PJ301_THONKICONN6"))
    )
    (comp (ref "OUTPUT2")
      (value "PJ301_THONKICONN6")
      (footprint "eagle-import:WQP_PJ_301M6")
      (libsource (lib "eagle-import") (part "PJ301_THONKICONN6"))
    )
    (comp (ref "R34")
      (value "100")
      (footprint "eagle-import:GMSN_M0805")
      (libsource (lib "eagle-import") (part "GMSN_R-US_M0805"))
    )
    (comp (ref "R57")
      (value "100")
      (footprint "eagle-import:GMSN_M0805")
      (libsource (lib "eagle-import") (part "GMSN_R-US_M0805"))
    )
    (comp (ref "R58")
      (value "100")
      (footprint "eagle-import:GMSN_M0805")
      (libsource (lib "eagle-import") (part "GMSN_R-US_M0805"))
    )
  )
  (nets
    (net (code "1") (name "-5V") (class "Default")
      (node (ref "IC4") (pin "1") (pinfunction "OUT_1") (pintype "output"))
      (node (ref "IC4") (pin "2") (pinfunction "-IN_2") (pintype "input"))
      (node (ref "R28") (pin "1") (pinfunction "1_1") (pintype "passive"))
      (node (ref "R29") (pin "1") (pinfunction "1_1") (pintype "passive"))
      (node (ref "R35") (pin "1") (pinfunction "1_1") (pintype "passive"))
      (node (ref "R61") (pin "1") (pinfunction "1_1") (pintype "passive"))
      (node (ref "R68") (pin "1") (pinfunction "1_1") (pintype "passive"))
    )
    (net (code "2") (name "-5VIN") (class "Default")
      (node (ref "C11") (pin "1") (pinfunction "1_1") (pintype "passive"))
      (node (ref "IC3") (pin "2") (pinfunction "A_2") (pintype "passive"))
      (node (ref "IC4") (pin "3") (pinfunction "+IN_3") (pintype "input"))
      (node (ref "R23") (pin "2") (pinfunction "2_2") (pintype "passive"))
    )
    (net (code "3") (name "-12V") (class "Default")
      (node (ref "C14") (pin "-") (pinfunction "-_-") (pintype "passive"))
      (node (ref "C2") (pin "2") (pinfunction "2_2") (pintype "passive"))
      (node (ref "C26") (pin "2") (pinfunction "2_2") (pintype "passive"))
      (node (ref "C28") (pin "2") (pinfunction "2_2") (pintype "passive"))
      (node (ref "C30") (pin "2") (pinfunction "2_2") (pintype "passive"))
      (node (ref "C32") (pin "2") (pinfunction "2_2") (pintype "passive"))
      (node (ref "C4") (pin "2") (pinfunction "2_2") (pintype "passive"))
      (node (ref "C6") (pin "2") (pinfunction "2_2") (pintype "passive"))
      (node (ref "D2") (pin "A") (pinfunction "A_A") (pintype "passive"))
      (node (ref "IC1") (pin "11") (pinfunction "V-_11") (pintype "power_in"))
      (node (ref "IC4") (pin "11") (pinfunction "V-_11") (pintype "power_in"))
      (node (ref "IC7") (pin "11") (pinfunction "V-_11") (pintype "power_in"))
      (node (ref "IC9") (pin "11") (pinfunction "V-_11") (pintype "power_in"))
      (node (ref "LED2") (pin "1") (pinfunction "C_1") (pintype "passive"))
      (node (ref "LED2") (pin "4") (pinfunction "A_4") (pintype "passive"))
      (node (ref "R13") (pin "2") (pinfunction "2_2") (pintype "passive"))
      (node (ref "R17") (pin "2") (pinfunction "2_2") (pintype "passive"))
      (node (ref "R23") (pin "1") (pinfunction "1_1") (pintype "passive"))
      (node (ref "R24") (pin "1") (pinfunction "1_1") (pintype "passive"))
      (node (ref "R30") (pin "2") (pinfunction "2_2") (pintype "passive"))
      (node (ref "R33") (pin "2") (pinfunction "2_2") (pintype "passive"))
      (node (ref "R42") (pin "1") (pinfunction "1_1") (pintype "passive"))
      (node (ref "R46") (pin "2") (pinfunction "2_2") (pintype "passive"))
      (node (ref "R47") (pin "2") (pinfunction "2_2") (pintype "passive"))
      (node (ref "R54") (pin "1") (pinfunction "1_1") (pintype "passive"))
    )
    (net (code "4") (name "5V") (class "Default")
      (node (ref "IC4") (pin "8") (pinfunction "OUT_8") (pintype "output"))
      (node (ref "R32") (pin "2") (pinfunction "2_2") (pintype "passive"))
      (node (ref "R69") (pin "2") (pinfunction "2_2") (pintype "passive"))
      (node (ref "R71") (pin "2") (pinfunction "2_2") (pintype "passive"))
      (node (ref "R73") (pin "2") (pinfunction "2_2") (pintype "passive"))
    )
    (net (code "5") (name "10V") (class "Default")
      (node (ref "IC4") (pin "7") (pinfunction "OUT_7") (pintype "output"))
      (node (ref "R1-F2") (pin "P$1") (pinfunction "E_P$1") (pintype "passive"))
      (node (ref "R31") (pin "2") (pinfunction "2_2") (pintype "passive"))
      (node (ref "R5-F1") (pin "P$1") (pinfunction "E_P$1") (pintype "passive"))
      (node (ref "R62-F3") (pin "P$1") (pinfunction "E_P$1") (pintype "passive"))
    )
    (net (code "6") (name "12V") (class "Default")
      (node (ref "C1") (pin "1") (pinfunction "1_1") (pintype "passive"))
      (node (ref "C13") (pin "+") (pinfunction "+_+") (pintype "passive"))
      (node (ref "C25") (pin "1") (pinfunction "1_1") (pintype "passive"))
      (node (ref "C27") (pin "1") (pinfunction "1_1") (pintype "passive"))
      (node (ref "C29") (pin "1") (pinfunction "1_1") (pintype "passive"))
      (node (ref "C3") (pin "1") (pinfunction "1_1") (pintype "passive"))
      (node (ref "C31") (pin "1") (pinfunction "1_1") (pintype "passive"))
      (node (ref "C5") (pin "1") (pinfunction "1_1") (pintype "passive"))
      (node (ref "D1") (pin "C") (pinfunction "C_C") (pintype "passive"))
      (node (ref "IC1") (pin "4") (pinfunction "V+_4") (pintype "power_in"))
      (node (ref "IC2") (pin "14") (pinfunction "14_14") (pintype "power_in"))
      (node (ref "IC4") (pin "4") (pinfunction "V+_4") (pintype "power_in"))
      (node (ref "IC5") (pin "14") (pinfunction "14_14") (pintype "power_in"))
      (node (ref "IC6") (pin "14") (pinfunction "14_14") (pintype "power_in"))
      (node (ref "IC7") (pin "4") (pinfunction "V+_4") (pintype "power_in"))
      (node (ref "IC9") (pin "4") (pinfunction "V+_4") (pintype "power_in"))
      (node (ref "R1") (pin "2") (pinfunction "2_2") (pintype "passive"))
    )
    (net (code "7") (name "BANDPASS_IN") (class "Default")
      (node (ref "C15") (pin "1") (pinfunction "1_1") (pintype "passive"))
      (node (ref "C19") (pin "1") (pinfunction "1_1") (pintype "passive"))
      (node (ref "C24") (pin "1") (pinfunction "1_1") (pintype "passive"))
      (node (ref "IC9") (pin "7") (pinfunction "OUT_7") (pintype "output"))
      (node (ref "R5") (pin "1") (pinfunction "1_1") (pintype "passive"))
    )
    (net (code "8") (name "BANDPASS_OUT1") (class "Default")
      (node (ref "C12") (pin "-") (pinfunction "-_-") (pintype "passive"))
      (node (ref "IC7") (pin "5") (pinfunction "+IN_5") (pintype "input"))
      (node (ref "R27") (pin "1") (pinfunction "1_1") (pintype "passive"))
    )
    (net (code "9") (name "BANDPASS_OUT2") (class "Default")
      (node (ref "C18") (pin "-") (pinfunction "-_-") (pintype "passive"))
      (node (ref "IC7") (pin "2") (pinfunction "-IN_2") (pintype "input"))
      (node (ref "R40") (pin "1") (pinfunction "1_1") (pintype "passive"))
    )
    (net (code "10") (name "BANDPASS_OUT3") (class "Default")
      (node (ref "C23") (pin "-") (pinfunction "-_-") (pintype "passive"))
      (node (ref "IC7") (pin "9") (pinfunction "-IN_9") (pintype "input"))
      (node (ref "R52") (pin "1") (pinfunction "1_1") (pintype "passive"))
    )
    (net (code "11") (name "FREQ_IN1") (class "Default")
      (node (ref "IC2") (pin "12") (pinfunction "12_12") (pintype "bidirectional"))
      (node (ref "R11") (pin "2") (pinfunction "2_2") (pintype "passive"))
      (node (ref "R26") (pin "1") (pinfunction "1_1") (pintype "passive"))
    )
    (net (code "12") (name "FREQ_IN2") (class "Default")
      (node (ref "IC5") (pin "12") (pinfunction "12_12") (pintype "bidirectional"))
      (node (ref "R41") (pin "1") (pinfunction "1_1") (pintype "passive"))
      (node (ref "R7") (pin "2") (pinfunction "2_2") (pintype "passive"))
    )
    (net (code "13") (name "FREQ_IN3") (class "Default")
      (node (ref "IC6") (pin "12") (pinfunction "12_12") (pintype "bidirectional"))
      (node (ref "R53") (pin "1") (pinfunction "1_1") (pintype "passive"))
      (node (ref "R65") (pin "2") (pinfunction "2_2") (pintype "passive"))
    )
    (net (code "14") (name "GND") (class "Default")
      (node (ref "C1") (pin "2") (pinfunction "2_2") (pintype "passive"))
      (node (ref "C10") (pin "2") (pinfunction "2_2") (pintype "passive"))
      (node (ref "C11") (pin "2") (pinfunction "2_2") (pintype "passive"))
      (node (ref "C13") (pin "-") (pinfunction "-_-") (pintype "passive"))
      (node (ref "C14") (pin "+") (pinfunction "+_+") (pintype "passive"))
      (node (ref "C17") (pin "2") (pinfunction "2_2") (pintype "passive"))
      (node (ref "C2") (pin "1") (pinfunction "1_1") (pintype "passive"))
      (node (ref "C20") (pin "2") (pinfunction "2_2") (pintype "passive"))
      (node (ref "C22") (pin "2") (pinfunction "2_2") (pintype "passive"))
      (node (ref "C25") (pin "2") (pinfunction "2_2") (pintype "passive"))
      (node (ref "C26") (pin "1") (pinfunction "1_1") (pintype "passive"))
      (node (ref "C27") (pin "2") (pinfunction "2_2") (pintype "passive"))
      (node (ref "C28") (pin "1") (pinfunction "1_1") (pintype "passive"))
      (node (ref "C29") (pin "2") (pinfunction "2_2") (pintype "passive"))
      (node (ref "C3") (pin "2") (pinfunction "2_2") (pintype "passive"))
      (node (ref "C30") (pin "1") (pinfunction "1_1") (pintype "passive"))
      (node (ref "C31") (pin "2") (pinfunction "2_2") (pintype "passive"))
      (node (ref "C32") (pin "1") (pinfunction "1_1") (pintype "passive"))
      (node (ref "C4") (pin "1") (pinfunction "1_1") (pintype "passive"))
      (node (ref "C5") (pin "2") (pinfunction "2_2") (pintype "passive"))
      (node (ref "C6") (pin "1") (pinfunction "1_1") (pintype "passive"))
      (node (ref "C7") (pin "2") (pinfunction "2_2") (pintype "passive"))
      (node (ref "C9") (pin "2") (pinfunction "2_2") (pintype "passive"))
      (node (ref "D5") (pin "1") (pinfunction "A_1") (pintype "passive"))
      (node (ref "D6") (pin "1") (pinfunction "A_1") (pintype "passive"))
      (node (ref "D8") (pin "1") (pinfunction "A_1") (pintype "passive"))
      (node (ref "IC1") (pin "3") (pinfunction "+IN_3") (pintype "input"))
      (node (ref "IC1") (pin "6") (pinfunction "-IN_6") (pintype "input"))
      (node (ref "IC1") (pin "9") (pinfunction "-IN_9") (pintype "input"))
      (node (ref "IC2") (pin "3") (pinfunction "3_3") (pintype "power_in"))
      (node (ref "IC3") (pin "1") (pinfunction "C_1") (pintype "passive"))
      (node (ref "IC4") (pin "10") (pinfunction "+IN_10") (pintype "input"))
      (node (ref "IC4") (pin "5") (pinfunction "+IN_5") (pintype "input"))
      (node (ref "IC5") (pin "3") (pinfunction "3_3") (pintype "power_in"))
      (node (ref "IC6") (pin "3") (pinfunction "3_3") (pintype "power_in"))
      (node (ref "IC9") (pin "5") (pinfunction "+IN_5") (pintype "input"))
      (node (ref "IN1") (pin "GND") (pinfunction "GND_GND") (pintype "passive"))
      (node (ref "IN1LEVEL") (pin "P$1") (pinfunction "1_P$1") (pintype "passive"))
      (node (ref "IN2") (pin "GND") (pinfunction "GND_GND") (pintype "passive"))
      (node (ref "IN2LEVEL") (pin "P$1") (pinfunction "1_P$1") (pintype "passive"))
      (node (ref "IN3") (pin "GND") (pinfunction "GND_GND") (pintype "passive"))
      (node (ref "IN3LEVEL") (pin "P$1") (pinfunction "1_P$1") (pintype "passive"))
      (node (ref "LED1") (pin "1") (pinfunction "C_1") (pintype "passive"))
      (node (ref "LED1") (pin "4") (pinfunction "A_4") (pintype "passive"))
      (node (ref "OUTPUT") (pin "P1") (pinfunction "1_P1") (pintype "passive"))
      (node (ref "OUTPUT1") (pin "P1") (pinfunction "1_P1") (pintype "passive"))
      (node (ref "OUTPUT2") (pin "P1") (pinfunction "1_P1") (pintype "passive"))
      (node (ref "POWER") (pin "3") (pinfunction "3_3") (pintype "passive"))
      (node (ref "POWER") (pin "4") (pinfunction "4_4") (pintype "passive"))
      (node (ref "POWER") (pin "5") (pinfunction "5_5") (pintype "passive"))
      (node (ref "POWER") (pin "6") (pinfunction "6_6") (pintype "passive"))
      (node (ref "POWER") (pin "7") (pinfunction "7_7") (pintype "passive"))
      (node (ref "POWER") (pin "8") (pinfunction "8_8") (pintype "passive"))
      (node (ref "R1-F2") (pin "P$3") (pinfunction "A_P$3") (pintype "passive"))
      (node (ref "R26") (pin "2") (pinfunction "2_2") (pintype "passive"))
      (node (ref "R4") (pin "2") (pinfunction "2_2") (pintype "passive"))
      (node (ref "R4-RES1") (pin "P$3") (pinfunction "A_P$3") (pintype "passive"))
      (node (ref "R41") (pin "2") (pinfunction "2_2") (pintype "passive"))
      (node (ref "R5-F1") (pin "P$3") (pinfunction "A_P$3") (pintype "passive"))
      (node (ref "R53") (pin "2") (pinfunction "2_2") (pintype "passive"))
      (node (ref "R55-RES2") (pin "P$3") (pinfunction "A_P$3") (pintype "passive"))
      (node (ref "R56-RES3") (pin "P$3") (pinfunction "A_P$3") (pintype "passive"))
      (node (ref "R62-F3") (pin "P$3") (pinfunction "A_P$3") (pintype "passive"))
      (node (ref "RES-1") (pin "P1") (pinfunction "1_P1") (pintype "passive"))
      (node (ref "RES-2") (pin "P1") (pinfunction "1_P1") (pintype "passive"))
      (node (ref "RES-3") (pin "P1") (pinfunction "1_P1") (pintype "passive"))
      (node (ref "V-OCT") (pin "P1") (pinfunction "1_P1") (pintype "passive"))
      (node (ref "V-OCT") (pin "P2") (pinfunction "2_P2") (pintype "passive"))
      (node (ref "V-OCT1") (pin "P1") (pinfunction "1_P1") (pintype "passive"))
      (node (ref "V-OCT1") (pin "P2") (pinfunction "2_P2") (pintype "passive"))
      (node (ref "V-OCT2") (pin "P1") (pinfunction "1_P1") (pintype "passive"))
      (node (ref "V-OCT2") (pin "P2") (pinfunction "2_P2") (pintype "passive"))
    )
    (net (code "15") (name "Net-(C7-Pad1)") (class "Default")
      (node (ref "C7") (pin "1") (pinfunction "1_1") (pintype "passive"))
      (node (ref "IC2") (pin "16") (pinfunction "16_16") (pintype "bidirectional"))
    )
    (net (code "16") (name "Net-(C8-Pad1)") (class "Default")
      (node (ref "C8") (pin "1") (pinfunction "1_1") (pintype "passive"))
      (node (ref "IC2") (pin "4") (pinfunction "4_4") (pintype "bidirectional"))
    )
    (net (code "17") (name "Net-(C8-Pad2)") (class "Default")
      (node (ref "C8") (pin "2") (pinfunction "2_2") (pintype "passive"))
      (node (ref "IC2") (pin "7") (pinfunction "7_7") (pintype "output"))
      (node (ref "R12") (pin "1") (pinfunction "1_1") (pintype "passive"))
    )
    (net (code "18") (name "Net-(C9-Pad1)") (class "Default")
      (node (ref "C9") (pin "1") (pinfunction "1_1") (pintype "passive"))
      (node (ref "IC5") (pin "16") (pinfunction "16_16") (pintype "bidirectional"))
    )
    (net (code "19") (name "Net-(C10-Pad1)") (class "Default")
      (node (ref "C10") (pin "1") (pinfunction "1_1") (pintype "passive"))
      (node (ref "IC2") (pin "11") (pinfunction "11_11") (pintype "output"))
    )
    (net (code "20") (name "Net-(C12-Pad+)") (class "Default")
      (node (ref "C12") (pin "+") (pinfunction "+_+") (pintype "passive"))
      (node (ref "IC2") (pin "10") (pinfunction "10_10") (pintype "output"))
      (node (ref "R21") (pin "1") (pinfunction "1_1") (pintype "passive"))
    )
    (net (code "21") (name "Net-(C15-Pad2)") (class "Default")
      (node (ref "C15") (pin "2") (pinfunction "2_2") (pintype "passive"))
      (node (ref "IC2") (pin "5") (pinfunction "5_5") (pintype "bidirectional"))
    )
    (net (code "22") (name "Net-(C16-Pad1)") (class "Default")
      (node (ref "C16") (pin "1") (pinfunction "1_1") (pintype "passive"))
      (node (ref "IC5") (pin "4") (pinfunction "4_4") (pintype "bidirectional"))
    )
    (net (code "23") (name "Net-(C16-Pad2)") (class "Default")
      (node (ref "C16") (pin "2") (pinfunction "2_2") (pintype "passive"))
      (node (ref "IC5") (pin "7") (pinfunction "7_7") (pintype "output"))
      (node (ref "R16") (pin "1") (pinfunction "1_1") (pintype "passive"))
    )
    (net (code "24") (name "Net-(C17-Pad1)") (class "Default")
      (node (ref "C17") (pin "1") (pinfunction "1_1") (pintype "passive"))
      (node (ref "IC5") (pin "11") (pinfunction "11_11") (pintype "output"))
    )
    (net (code "25") (name "Net-(C18-Pad+)") (class "Default")
      (node (ref "C18") (pin "+") (pinfunction "+_+") (pintype "passive"))
      (node (ref "IC5") (pin "10") (pinfunction "10_10") (pintype "output"))
      (node (ref "R14") (pin "1") (pinfunction "1_1") (pintype "passive"))
    )
    (net (code "26") (name "Net-(C19-Pad2)") (class "Default")
      (node (ref "C19") (pin "2") (pinfunction "2_2") (pintype "passive"))
      (node (ref "IC5") (pin "5") (pinfunction "5_5") (pintype "bidirectional"))
    )
    (net (code "27") (name "Net-(C20-Pad1)") (class "Default")
      (node (ref "C20") (pin "1") (pinfunction "1_1") (pintype "passive"))
      (node (ref "IC6") (pin "16") (pinfunction "16_16") (pintype "bidirectional"))
    )
    (net (code "28") (name "Net-(C21-Pad1)") (class "Default")
      (node (ref "C21") (pin "1") (pinfunction "1_1") (pintype "passive"))
      (node (ref "IC6") (pin "4") (pinfunction "4_4") (pintype "bidirectional"))
    )
    (net (code "29") (name "Net-(C21-Pad2)") (class "Default")
      (node (ref "C21") (pin "2") (pinfunction "2_2") (pintype "passive"))
      (node (ref "IC6") (pin "7") (pinfunction "7_7") (pintype "output"))
      (node (ref "R45") (pin "1") (pinfunction "1_1") (pintype "passive"))
    )
    (net (code "30") (name "Net-(C22-Pad1)") (class "Default")
      (node (ref "C22") (pin "1") (pinfunction "1_1") (pintype "passive"))
      (node (ref "IC6") (pin "11") (pinfunction "11_11") (pintype "output"))
    )
    (net (code "31") (name "Net-(C23-Pad+)") (class "Default")
      (node (ref "C23") (pin "+") (pinfunction "+_+") (pintype "passive"))
      (node (ref "IC6") (pin "10") (pinfunction "10_10") (pintype "output"))
      (node (ref "R43") (pin "1") (pinfunction "1_1") (pintype "passive"))
    )
    (net (code "32") (name "Net-(C24-Pad2)") (class "Default")
      (node (ref "C24") (pin "2") (pinfunction "2_2") (pintype "passive"))
      (node (ref "IC6") (pin "5") (pinfunction "5_5") (pintype "bidirectional"))
    )
    (net (code "33") (name "Net-(D1-PadA)") (class "Default")
      (node (ref "D1") (pin "A") (pinfunction "A_A") (pintype "passive"))
      (node (ref "POWER") (pin "10") (pinfunction "10_10") (pintype "passive"))
      (node (ref "POWER") (pin "9") (pinfunction "9_9") (pintype "passive"))
    )
    (net (code "34") (name "Net-(D2-PadC)") (class "Default")
      (node (ref "D2") (pin "C") (pinfunction "C_C") (pintype "passive"))
      (node (ref "POWER") (pin "1") (pinfunction "1_1") (pintype "passive"))
      (node (ref "POWER") (pin "2") (pinfunction "2_2") (pintype "passive"))
    )
    (net (code "35") (name "Net-(D3-PadC)") (class "Default")
      (node (ref "D3") (pin "C") (pinfunction "C_C") (pintype "passive"))
      (node (ref "R72") (pin "2") (pinfunction "2_2") (pintype "passive"))
    )
    (net (code "36") (name "Net-(D4-PadC)") (class "Default")
      (node (ref "D4") (pin "C") (pinfunction "C_C") (pintype "passive"))
      (node (ref "R70") (pin "2") (pinfunction "2_2") (pintype "passive"))
    )
    (net (code "37") (name "Net-(D5-C)") (class "Default")
      (node (ref "D5") (pin "3") (pinfunction "C_3") (pintype "passive"))
      (node (ref "IC9") (pin "3") (pinfunction "+IN_3") (pintype "input"))
      (node (ref "R70") (pin "1") (pinfunction "1_1") (pintype "passive"))
    )
    (net (code "38") (name "Net-(D6-C)") (class "Default")
      (node (ref "D6") (pin "3") (pinfunction "C_3") (pintype "passive"))
      (node (ref "IC9") (pin "10") (pinfunction "+IN_10") (pintype "input"))
      (node (ref "R72") (pin "1") (pinfunction "1_1") (pintype "passive"))
    )
    (net (code "39") (name "Net-(D7-PadC)") (class "Default")
      (node (ref "D7") (pin "C") (pinfunction "C_C") (pintype "passive"))
      (node (ref "R74") (pin "2") (pinfunction "2_2") (pintype "passive"))
    )
    (net (code "40") (name "Net-(D8-C)") (class "Default")
      (node (ref "D8") (pin "3") (pinfunction "C_3") (pintype "passive"))
      (node (ref "IC1") (pin "13") (pinfunction "-IN_13") (pintype "input"))
      (node (ref "R74") (pin "1") (pinfunction "1_1") (pintype "passive"))
    )
    (net (code "41") (name "Net-(IC1A--IN)") (class "Default")
      (node (ref "IC1") (pin "2") (pinfunction "-IN_2") (pintype "input"))
      (node (ref "R35") (pin "2") (pinfunction "2_2") (pintype "passive"))
      (node (ref "R6") (pin "2") (pinfunction "2_2") (pintype "passive"))
      (node (ref "R8") (pin "2") (pinfunction "2_2") (pintype "passive"))
      (node (ref "R9") (pin "3") (pinfunction "A_3") (pintype "passive"))
    )
    (net (code "42") (name "Net-(IC1A-OUT)") (class "Default")
      (node (ref "IC1") (pin "1") (pinfunction "OUT_1") (pintype "output"))
      (node (ref "R10") (pin "2") (pinfunction "2_2") (pintype "passive"))
      (node (ref "R11") (pin "1") (pinfunction "1_1") (pintype "passive"))
    )
    (net (code "43") (name "Net-(IC1B-+IN)") (class "Default")
      (node (ref "IC1") (pin "5") (pinfunction "+IN_5") (pintype "input"))
      (node (ref "R2") (pin "2") (pinfunction "2_2") (pintype "passive"))
      (node (ref "R59") (pin "2") (pinfunction "2_2") (pintype "passive"))
      (node (ref "R60") (pin "3") (pinfunction "A_3") (pintype "passive"))
      (node (ref "R61") (pin "2") (pinfunction "2_2") (pintype "passive"))
    )
    (net (code "44") (name "Net-(IC1B-OUT)") (class "Default")
      (node (ref "IC1") (pin "7") (pinfunction "OUT_7") (pintype "output"))
      (node (ref "R3") (pin "2") (pinfunction "2_2") (pintype "passive"))
      (node (ref "R7") (pin "1") (pinfunction "1_1") (pintype "passive"))
    )
    (net (code "45") (name "Net-(IC1C-+IN)") (class "Default")
      (node (ref "IC1") (pin "10") (pinfunction "+IN_10") (pintype "input"))
      (node (ref "R63") (pin "2") (pinfunction "2_2") (pintype "passive"))
      (node (ref "R66") (pin "2") (pinfunction "2_2") (pintype "passive"))
      (node (ref "R67") (pin "3") (pinfunction "A_3") (pintype "passive"))
      (node (ref "R68") (pin "2") (pinfunction "2_2") (pintype "passive"))
    )
    (net (code "46") (name "Net-(IC1C-OUT)") (class "Default")
      (node (ref "IC1") (pin "8") (pinfunction "OUT_8") (pintype "output"))
      (node (ref "R64") (pin "2") (pinfunction "2_2") (pintype "passive"))
      (node (ref "R65") (pin "1") (pinfunction "1_1") (pintype "passive"))
    )
    (net (code "47") (name "Net-(IC2-Pad1)") (class "Default")
      (node (ref "IC2") (pin "1") (pinfunction "1_1") (pintype "input"))
      (node (ref "R12") (pin "2") (pinfunction "2_2") (pintype "passive"))
    )
    (net (code "48") (name "Net-(IC2-Pad2)") (class "Default")
      (node (ref "IC2") (pin "2") (pinfunction "2_2") (pintype "input"))
      (node (ref "R22") (pin "1") (pinfunction "1_1") (pintype "passive"))
    )
    (net (code "49") (name "Net-(IC2-Pad6)") (class "Default")
      (node (ref "IC2") (pin "6") (pinfunction "6_6") (pintype "output"))
      (node (ref "R20") (pin "2") (pinfunction "2_2") (pintype "passive"))
      (node (ref "R22") (pin "2") (pinfunction "2_2") (pintype "passive"))
    )
    (net (code "50") (name "Net-(IC2-Pad8)") (class "Default")
      (node (ref "IC2") (pin "8") (pinfunction "8_8") (pintype "input"))
      (node (ref "R27") (pin "2") (pinfunction "2_2") (pintype "passive"))
    )
    (net (code "51") (name "Net-(IC2-Pad9)") (class "Default")
      (node (ref "IC2") (pin "9") (pinfunction "9_9") (pintype "input"))
      (node (ref "R25") (pin "1") (pinfunction "1_1") (pintype "passive"))
    )
    (net (code "52") (name "Net-(IC2-Pad13)") (class "Default")
      (node (ref "IC2") (pin "13") (pinfunction "13_13") (pintype "power_in"))
      (node (ref "R24") (pin "2") (pinfunction "2_2") (pintype "passive"))
    )
    (net (code "53") (name "Net-(IC2-Pad15)") (class "Default")
      (node (ref "IC2") (pin "15") (pinfunction "15_15") (pintype "output"))
      (node (ref "R18") (pin "1") (pinfunction "1_1") (pintype "passive"))
      (node (ref "R19") (pin "1") (pinfunction "1_1") (pintype "passive"))
    )
    (net (code "54") (name "Net-(IC2-Pad17)") (class "Default")
      (node (ref "IC2") (pin "17") (pinfunction "17_17") (pintype "input"))
      (node (ref "R17") (pin "1") (pinfunction "1_1") (pintype "passive"))
      (node (ref "R18") (pin "2") (pinfunction "2_2") (pintype "passive"))
      (node (ref "R20") (pin "1") (pinfunction "1_1") (pintype "passive"))
    )
    (net (code "55") (name "Net-(IC2-Pad18)") (class "Default")
      (node (ref "IC2") (pin "18") (pinfunction "18_18") (pintype "input"))
      (node (ref "R13") (pin "1") (pinfunction "1_1") (pintype "passive"))
      (node (ref "R19") (pin "2") (pinfunction "2_2") (pintype "passive"))
      (node (ref "R21") (pin "2") (pinfunction "2_2") (pintype "passive"))
    )
    (net (code "56") (name "Net-(IC4B--IN)") (class "Default")
      (node (ref "IC4") (pin "6") (pinfunction "-IN_6") (pintype "input"))
      (node (ref "R28") (pin "2") (pinfunction "2_2") (pintype "passive"))
      (node (ref "R31") (pin "1") (pinfunction "1_1") (pintype "passive"))
    )
    (net (code "57") (name "Net-(IC4C--IN)") (class "Default")
      (node (ref "IC4") (pin "9") (pinfunction "-IN_9") (pintype "input"))
      (node (ref "R29") (pin "2") (pinfunction "2_2") (pintype "passive"))
      (node (ref "R32") (pin "1") (pinfunction "1_1") (pintype "passive"))
    )
    (net (code "58") (name "Net-(IC5-Pad1)") (class "Default")
      (node (ref "IC5") (pin "1") (pinfunction "1_1") (pintype "input"))
      (node (ref "R16") (pin "2") (pinfunction "2_2") (pintype "passive"))
    )
    (net (code "59") (name "Net-(IC5-Pad2)") (class "Default")
      (node (ref "IC5") (pin "2") (pinfunction "2_2") (pintype "input"))
      (node (ref "R38") (pin "1") (pinfunction "1_1") (pintype "passive"))
    )
    (net (code "60") (name "Net-(IC5-Pad6)") (class "Default")
      (node (ref "IC5") (pin "6") (pinfunction "6_6") (pintype "output"))
      (node (ref "R37") (pin "2") (pinfunction "2_2") (pintype "passive"))
      (node (ref "R38") (pin "2") (pinfunction "2_2") (pintype "passive"))
    )
    (net (code "61") (name "Net-(IC5-Pad8)") (class "Default")
      (node (ref "IC5") (pin "8") (pinfunction "8_8") (pintype "input"))
      (node (ref "R40") (pin "2") (pinfunction "2_2") (pintype "passive"))
    )
    (net (code "62") (name "Net-(IC5-Pad9)") (class "Default")
      (node (ref "IC5") (pin "9") (pinfunction "9_9") (pintype "input"))
      (node (ref "R39") (pin "1") (pinfunction "1_1") (pintype "passive"))
    )
    (net (code "63") (name "Net-(IC5-Pad13)") (class "Default")
      (node (ref "IC5") (pin "13") (pinfunction "13_13") (pintype "power_in"))
      (node (ref "R42") (pin "2") (pinfunction "2_2") (pintype "passive"))
    )
    (net (code "64") (name "Net-(IC5-Pad15)") (class "Default")
      (node (ref "IC5") (pin "15") (pinfunction "15_15") (pintype "output"))
      (node (ref "R15") (pin "1") (pinfunction "1_1") (pintype "passive"))
      (node (ref "R36") (pin "1") (pinfunction "1_1") (pintype "passive"))
    )
    (net (code "65") (name "Net-(IC5-Pad17)") (class "Default")
      (node (ref "IC5") (pin "17") (pinfunction "17_17") (pintype "input"))
      (node (ref "R30") (pin "1") (pinfunction "1_1") (pintype "passive"))
      (node (ref "R36") (pin "2") (pinfunction "2_2") (pintype "passive"))
      (node (ref "R37") (pin "1") (pinfunction "1_1") (pintype "passive"))
    )
    (net (code "66") (name "Net-(IC5-Pad18)") (class "Default")
      (node (ref "IC5") (pin "18") (pinfunction "18_18") (pintype "input"))
      (node (ref "R14") (pin "2") (pinfunction "2_2") (pintype "passive"))
      (node (ref "R15") (pin "2") (pinfunction "2_2") (pintype "passive"))
      (node (ref "R33") (pin "1") (pinfunction "1_1") (pintype "passive"))
    )
    (net (code "67") (name "Net-(IC6-Pad1)") (class "Default")
      (node (ref "IC6") (pin "1") (pinfunction "1_1") (pintype "input"))
      (node (ref "R45") (pin "2") (pinfunction "2_2") (pintype "passive"))
    )
    (net (code "68") (name "Net-(IC6-Pad2)") (class "Default")
      (node (ref "IC6") (pin "2") (pinfunction "2_2") (pintype "input"))
      (node (ref "R50") (pin "1") (pinfunction "1_1") (pintype "passive"))
    )
    (net (code "69") (name "Net-(IC6-Pad6)") (class "Default")
      (node (ref "IC6") (pin "6") (pinfunction "6_6") (pintype "output"))
      (node (ref "R49") (pin "2") (pinfunction "2_2") (pintype "passive"))
      (node (ref "R50") (pin "2") (pinfunction "2_2") (pintype "passive"))
    )
    (net (code "70") (name "Net-(IC6-Pad8)") (class "Default")
      (node (ref "IC6") (pin "8") (pinfunction "8_8") (pintype "input"))
      (node (ref "R52") (pin "2") (pinfunction "2_2") (pintype "passive"))
    )
    (net (code "71") (name "Net-(IC6-Pad9)") (class "Default")
      (node (ref "IC6") (pin "9") (pinfunction "9_9") (pintype "input"))
      (node (ref "R51") (pin "1") (pinfunction "1_1") (pintype "passive"))
    )
    (net (code "72") (name "Net-(IC6-Pad13)") (class "Default")
      (node (ref "IC6") (pin "13") (pinfunction "13_13") (pintype "power_in"))
      (node (ref "R54") (pin "2") (pinfunction "2_2") (pintype "passive"))
    )
    (net (code "73") (name "Net-(IC6-Pad15)") (class "Default")
      (node (ref "IC6") (pin "15") (pinfunction "15_15") (pintype "output"))
      (node (ref "R44") (pin "1") (pinfunction "1_1") (pintype "passive"))
      (node (ref "R48") (pin "1") (pinfunction "1_1") (pintype "passive"))
    )
    (net (code "74") (name "Net-(IC6-Pad17)") (class "Default")
      (node (ref "IC6") (pin "17") (pinfunction "17_17") (pintype "input"))
      (node (ref "R46") (pin "1") (pinfunction "1_1") (pintype "passive"))
      (node (ref "R48") (pin "2") (pinfunction "2_2") (pintype "passive"))
      (node (ref "R49") (pin "1") (pinfunction "1_1") (pintype "passive"))
    )
    (net (code "75") (name "Net-(IC6-Pad18)") (class "Default")
      (node (ref "IC6") (pin "18") (pinfunction "18_18") (pintype "input"))
      (node (ref "R43") (pin "2") (pinfunction "2_2") (pintype "passive"))
      (node (ref "R44") (pin "2") (pinfunction "2_2") (pintype "passive"))
      (node (ref "R47") (pin "1") (pinfunction "1_1") (pintype "passive"))
    )
    (net (code "76") (name "Net-(IC7A-+IN)") (class "Default")
      (node (ref "IC7") (pin "1") (pinfunction "OUT_1") (pintype "output"))
      (node (ref "IC7") (pin "3") (pinfunction "+IN_3") (pintype "input"))
      (node (ref "R57") (pin "1") (pinfunction "1_1") (pintype "passive"))
    )
    (net (code "77") (name "Net-(IC7B--IN)") (class "Default")
      (node (ref "IC7") (pin "6") (pinfunction "-IN_6") (pintype "input"))
      (node (ref "IC7") (pin "7") (pinfunction "OUT_7") (pintype "output"))
      (node (ref "R34") (pin "1") (pinfunction "1_1") (pintype "passive"))
    )
    (net (code "78") (name "Net-(IC7C-+IN)") (class "Default")
      (node (ref "IC7") (pin "10") (pinfunction "+IN_10") (pintype "input"))
      (node (ref "IC7") (pin "8") (pinfunction "OUT_8") (pintype "output"))
      (node (ref "R58") (pin "1") (pinfunction "1_1") (pintype "passive"))
    )
    (net (code "79") (name "Net-(IC9B--IN)") (class "Default")
      (node (ref "IC9") (pin "6") (pinfunction "-IN_6") (pintype "input"))
      (node (ref "R5") (pin "2") (pinfunction "2_2") (pintype "passive"))
      (node (ref "R55") (pin "1") (pinfunction "1_1") (pintype "passive"))
      (node (ref "R56") (pin "1") (pinfunction "1_1") (pintype "passive"))
      (node (ref "R62") (pin "1") (pinfunction "1_1") (pintype "passive"))
    )
    (net (code "80") (name "Net-(IN1LEVEL-2)") (class "Default")
      (node (ref "IN1LEVEL") (pin "P$2") (pinfunction "2_P$2") (pintype "passive"))
      (node (ref "R55") (pin "2") (pinfunction "2_2") (pintype "passive"))
    )
    (net (code "81") (name "Net-(IN1LEVEL-3)") (class "Default")
      (node (ref "IN1") (pin "TIP") (pinfunction "TIP_TIP") (pintype "passive"))
      (node (ref "IN1LEVEL") (pin "P$3") (pinfunction "3_P$3") (pintype "passive"))
    )
    (net (code "82") (name "Net-(IN2LEVEL-2)") (class "Default")
      (node (ref "IN2LEVEL") (pin "P$2") (pinfunction "2_P$2") (pintype "passive"))
      (node (ref "R56") (pin "2") (pinfunction "2_2") (pintype "passive"))
    )
    (net (code "83") (name "Net-(IN2LEVEL-3)") (class "Default")
      (node (ref "IN2") (pin "TIP") (pinfunction "TIP_TIP") (pintype "passive"))
      (node (ref "IN2LEVEL") (pin "P$3") (pinfunction "3_P$3") (pintype "passive"))
    )
    (net (code "84") (name "Net-(IN3LEVEL-2)") (class "Default")
      (node (ref "IN3LEVEL") (pin "P$2") (pinfunction "2_P$2") (pintype "passive"))
      (node (ref "R62") (pin "2") (pinfunction "2_2") (pintype "passive"))
    )
    (net (code "85") (name "Net-(IN3LEVEL-3)") (class "Default")
      (node (ref "IN3") (pin "TIP") (pinfunction "TIP_TIP") (pintype "passive"))
      (node (ref "IN3LEVEL") (pin "P$3") (pinfunction "3_P$3") (pintype "passive"))
    )
    (net (code "86") (name "Net-(LED1A-A)") (class "Default")
      (node (ref "LED1") (pin "2") (pinfunction "A_2") (pintype "passive"))
      (node (ref "LED1") (pin "3") (pinfunction "C_3") (pintype "passive"))
      (node (ref "R1") (pin "1") (pinfunction "1_1") (pintype "passive"))
    )
    (net (code "87") (name "Net-(LED2A-A)") (class "Default")
      (node (ref "LED2") (pin "2") (pinfunction "A_2") (pintype "passive"))
      (node (ref "LED2") (pin "3") (pinfunction "C_3") (pintype "passive"))
      (node (ref "R4") (pin "1") (pinfunction "1_1") (pintype "passive"))
    )
    (net (code "88") (name "Net-(OUTPUT-3)") (class "Default")
      (node (ref "OUTPUT") (pin "P3") (pinfunction "3_P3") (pintype "passive"))
      (node (ref "R34") (pin "2") (pinfunction "2_2") (pintype "passive"))
    )
    (net (code "89") (name "Net-(OUTPUT1-3)") (class "Default")
      (node (ref "OUTPUT1") (pin "P3") (pinfunction "3_P3") (pintype "passive"))
      (node (ref "R57") (pin "2") (pinfunction "2_2") (pintype "passive"))
    )
    (net (code "90") (name "Net-(OUTPUT2-3)") (class "Default")
      (node (ref "OUTPUT2") (pin "P3") (pinfunction "3_P3") (pintype "passive"))
      (node (ref "R58") (pin "2") (pinfunction "2_2") (pintype "passive"))
    )
    (net (code "91") (name "Net-(R1-F2-S)") (class "Default")
      (node (ref "R1-F2") (pin "P$2") (pinfunction "S_P$2") (pintype "passive"))
      (node (ref "R2") (pin "1") (pinfunction "1_1") (pintype "passive"))
    )
    (net (code "92") (name "Net-(R5-F1-S)") (class "Default")
      (node (ref "R5-F1") (pin "P$2") (pinfunction "S_P$2") (pintype "passive"))
      (node (ref "R6") (pin "1") (pinfunction "1_1") (pintype "passive"))
    )
    (net (code "93") (name "Net-(R9-E)") (class "Default")
      (node (ref "R10") (pin "1") (pinfunction "1_1") (pintype "passive"))
      (node (ref "R9") (pin "1") (pinfunction "E_1") (pintype "passive"))
      (node (ref "R9") (pin "2") (pinfunction "S_2") (pintype "passive"))
    )
    (net (code "94") (name "Net-(R60-E)") (class "Default")
      (node (ref "R3") (pin "1") (pinfunction "1_1") (pintype "passive"))
      (node (ref "R60") (pin "1") (pinfunction "E_1") (pintype "passive"))
      (node (ref "R60") (pin "2") (pinfunction "S_2") (pintype "passive"))
    )
    (net (code "95") (name "Net-(R62-F3-S)") (class "Default")
      (node (ref "R62-F3") (pin "P$2") (pinfunction "S_P$2") (pintype "passive"))
      (node (ref "R63") (pin "1") (pinfunction "1_1") (pintype "passive"))
    )
    (net (code "96") (name "Net-(R67-E)") (class "Default")
      (node (ref "R64") (pin "1") (pinfunction "1_1") (pintype "passive"))
      (node (ref "R67") (pin "1") (pinfunction "E_1") (pintype "passive"))
      (node (ref "R67") (pin "2") (pinfunction "S_2") (pintype "passive"))
    )
    (net (code "97") (name "Net-(RES-1-2)") (class "Default")
      (node (ref "R69") (pin "1") (pinfunction "1_1") (pintype "passive"))
      (node (ref "RES-1") (pin "P2") (pinfunction "2_P2") (pintype "passive"))
    )
    (net (code "98") (name "Net-(RES-1-3)") (class "Default")
      (node (ref "D4") (pin "A") (pinfunction "A_A") (pintype "passive"))
      (node (ref "RES-1") (pin "P3") (pinfunction "3_P3") (pintype "passive"))
    )
    (net (code "99") (name "Net-(RES-2-2)") (class "Default")
      (node (ref "R71") (pin "1") (pinfunction "1_1") (pintype "passive"))
      (node (ref "RES-2") (pin "P2") (pinfunction "2_P2") (pintype "passive"))
    )
    (net (code "100") (name "Net-(RES-2-3)") (class "Default")
      (node (ref "D3") (pin "A") (pinfunction "A_A") (pintype "passive"))
      (node (ref "RES-2") (pin "P3") (pinfunction "3_P3") (pintype "passive"))
    )
    (net (code "101") (name "Net-(RES-3-2)") (class "Default")
      (node (ref "R73") (pin "1") (pinfunction "1_1") (pintype "passive"))
      (node (ref "RES-3") (pin "P2") (pinfunction "2_P2") (pintype "passive"))
    )
    (net (code "102") (name "Net-(RES-3-3)") (class "Default")
      (node (ref "D7") (pin "A") (pinfunction "A_A") (pintype "passive"))
      (node (ref "RES-3") (pin "P3") (pinfunction "3_P3") (pintype "passive"))
    )
    (net (code "103") (name "Net-(V-OCT-3)") (class "Default")
      (node (ref "R8") (pin "1") (pinfunction "1_1") (pintype "passive"))
      (node (ref "V-OCT") (pin "P3") (pinfunction "3_P3") (pintype "passive"))
    )
    (net (code "104") (name "Net-(V-OCT1-3)") (class "Default")
      (node (ref "R59") (pin "1") (pinfunction "1_1") (pintype "passive"))
      (node (ref "V-OCT1") (pin "P3") (pinfunction "3_P3") (pintype "passive"))
    )
    (net (code "105") (name "Net-(V-OCT2-3)") (class "Default")
      (node (ref "R66") (pin "1") (pinfunction "1_1") (pintype "passive"))
      (node (ref "V-OCT2") (pin "P3") (pinfunction "3_P3") (pintype "passive"))
    )
    (net (code "106") (name "RESONANCE_CTL1") (class "Default")
      (node (ref "R25") (pin "2") (pinfunction "2_2") (pintype "passive"))
      (node (ref "R4-RES1") (pin "P$2") (pinfunction "S_P$2") (pintype "passive"))
    )
    (net (code "107") (name "RESONANCE_CTL2") (class "Default")
      (node (ref "R39") (pin "2") (pinfunction "2_2") (pintype "passive"))
      (node (ref "R55-RES2") (pin "P$2") (pinfunction "S_P$2") (pintype "passive"))
    )
    (net (code "108") (name "RESONANCE_CTL3") (class "Default")
      (node (ref "R51") (pin "2") (pinfunction "2_2") (pintype "passive"))
      (node (ref "R56-RES3") (pin "P$2") (pinfunction "S_P$2") (pintype "passive"))
    )
    (net (code "109") (name "RESONANCE_IN1") (class "Default")
      (node (ref "IC9") (pin "1") (pinfunction "OUT_1") (pintype "output"))
      (node (ref "IC9") (pin "2") (pinfunction "-IN_2") (pintype "input"))
      (node (ref "R4-RES1") (pin "P$1") (pinfunction "E_P$1") (pintype "passive"))
    )
    (net (code "110") (name "RESONANCE_IN2") (class "Default")
      (node (ref "IC9") (pin "8") (pinfunction "OUT_8") (pintype "output"))
      (node (ref "IC9") (pin "9") (pinfunction "-IN_9") (pintype "input"))
      (node (ref "R55-RES2") (pin "P$1") (pinfunction "E_P$1") (pintype "passive"))
    )
    (net (code "111") (name "RESONANCE_IN3") (class "Default")
      (node (ref "IC1") (pin "12") (pinfunction "+IN_12") (pintype "input"))
      (node (ref "IC1") (pin "14") (pinfunction "OUT_14") (pintype "output"))
      (node (ref "R56-RES3") (pin "P$1") (pinfunction "E_P$1") (pintype "passive"))
    )
    (net (code "112") (name "unconnected-(IN1-PadNORM)") (class "Default")
      (node (ref "IN1") (pin "NORM") (pinfunction "NORM_NORM") (pintype "passive"))
    )
    (net (code "113") (name "unconnected-(IN2-PadNORM)") (class "Default")
      (node (ref "IN2") (pin "NORM") (pinfunction "NORM_NORM") (pintype "passive"))
    )
    (net (code "114") (name "unconnected-(IN3-PadNORM)") (class "Default")
      (node (ref "IN3") (pin "NORM") (pinfunction "NORM_NORM") (pintype "passive"))
    )
    (net (code "115") (name "unconnected-(OUTPUT-2-PadP2)") (class "Default")
      (node (ref "OUTPUT") (pin "P2") (pinfunction "2_P2") (pintype "passive"))
    )
    (net (code "116") (name "unconnected-(OUTPUT1-2-PadP2)") (class "Default")
      (node (ref "OUTPUT1") (pin "P2") (pinfunction "2_P2") (pintype "passive"))
    )
    (net (code "117") (name "unconnected-(OUTPUT2-2-PadP2)") (class "Default")
      (node (ref "OUTPUT2") (pin "P2") (pinfunction "2_P2") (pintype "passive"))
    )
  )
)
